# round_paws_2.net
KiCad netlist of a schematic drawn in EAGLE
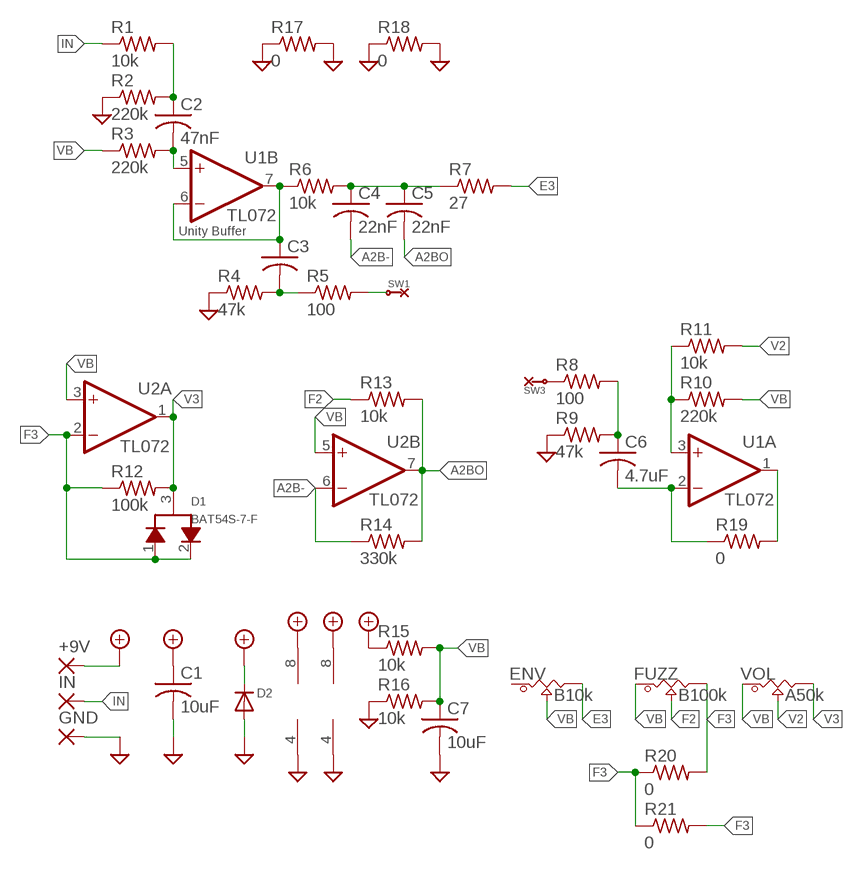
[diagram p0: schematic, sheet 1]

(export (version "E")
  (design (tool "Eeschema 10.0.6"))
  (components
    (comp (ref "+9V")
      (value "SMD2")
      (footprint "eagle-import:SMD1,27-2,54")
      (libsource (lib "eagle-import") (part "SMD2"))
    )
    (comp (ref "C1")
      (value "10uF")
      (footprint "eagle-import:C1206")
      (libsource (lib "eagle-import") (part "C-USC1206"))
    )
    (comp (ref "C2")
      (value "47nF")
      (footprint "eagle-import:C0603")
      (libsource (lib "eagle-import") (part "C-USC0603"))
    )
    (comp (ref "C3")
      (value "C-USC0603")
      (footprint "eagle-import:C0603")
      (libsource (lib "eagle-import") (part "C-USC0603"))
    )
    (comp (ref "C4")
      (value "22nF")
      (footprint "eagle-import:C0603")
      (libsource (lib "eagle-import") (part "C-USC0603"))
    )
    (comp (ref "C5")
      (value "22nF")
      (footprint "eagle-import:C0603")
      (libsource (lib "eagle-import") (part "C-USC0603"))
    )
    (comp (ref "C6")
      (value "4.7uF")
      (footprint "eagle-import:C1206")
      (libsource (lib "eagle-import") (part "C-USC1206"))
    )
    (comp (ref "C7")
      (value "10uF")
      (footprint "eagle-import:C1206")
      (libsource (lib "eagle-import") (part "C-USC1206"))
    )
    (comp (ref "D1")
      (value "BAT54S-7-F")
      (footprint "eagle-import:SOT23-3")
      (fields
        (field (name "DIGIKEY_PART_NUMBER") "BAT54S-FDITR-ND")
        (field (name "MANUFACTURER") "Diodes Incorporated")
        (field (name "CREATED_BY") "PCBLayout.com")
      )
      (libsource (lib "eagle-import") (part "BAT54S-7-F"))
    )
    (comp (ref "D2")
      (value "DIODESOD-123")
      (footprint "eagle-import:SOD-123")
      (libsource (lib "eagle-import") (part "DIODESOD-123"))
    )
    (comp (ref "ENV")
      (value "B10k")
      (footprint "eagle-import:POT_9MM_SMD")
      (libsource (lib "eagle-import") (part "POT_9MM_SMD"))
    )
    (comp (ref "FUZZ")
      (value "B100k")
      (footprint "eagle-import:POT_9MM_SMD")
      (libsource (lib "eagle-import") (part "POT_9MM_SMD"))
    )
    (comp (ref "GND")
      (value "SMD2")
      (footprint "eagle-import:SMD1,27-2,54")
      (libsource (lib "eagle-import") (part "SMD2"))
    )
    (comp (ref "IN")
      (value "SMD2")
      (footprint "eagle-import:SMD1,27-2,54")
      (libsource (lib "eagle-import") (part "SMD2"))
    )
    (comp (ref "R1")
      (value "10k")
      (footprint "eagle-import:R0603")
      (libsource (lib "eagle-import") (part "R-US_R0603"))
    )
    (comp (ref "R2")
      (value "220k")
      (footprint "eagle-import:R0603")
      (libsource (lib "eagle-import") (part "R-US_R0603"))
    )
    (comp (ref "R3")
      (value "220k")
      (footprint "eagle-import:R0603")
      (libsource (lib "eagle-import") (part "R-US_R0603"))
    )
    (comp (ref "R4")
      (value "47k")
      (footprint "eagle-import:R0603")
      (libsource (lib "eagle-import") (part "R-US_R0603"))
    )
    (comp (ref "R5")
      (value "100")
      (footprint "eagle-import:R0603")
      (libsource (lib "eagle-import") (part "R-US_R0603"))
    )
    (comp (ref "R6")
      (value "10k")
      (footprint "eagle-import:R0603")
      (libsource (lib "eagle-import") (part "R-US_R0603"))
    )
    (comp (ref "R7")
      (value "27")
      (footprint "eagle-import:R0603")
      (libsource (lib "eagle-import") (part "R-US_R0603"))
    )
    (comp (ref "R8")
      (value "100")
      (footprint "eagle-import:R0603")
      (libsource (lib "eagle-import") (part "R-US_R0603"))
    )
    (comp (ref "R9")
      (value "47k")
      (footprint "eagle-import:R0603")
      (libsource (lib "eagle-import") (part "R-US_R0603"))
    )
    (comp (ref "R10")
      (value "220k")
      (footprint "eagle-import:R0603")
      (libsource (lib "eagle-import") (part "R-US_R0603"))
    )
    (comp (ref "R11")
      (value "10k")
      (footprint "eagle-import:R0603")
      (libsource (lib "eagle-import") (part "R-US_R0603"))
    )
    (comp (ref "R12")
      (value "100k")
      (footprint "eagle-import:R0603")
      (libsource (lib "eagle-import") (part "R-US_R0603"))
    )
    (comp (ref "R13")
      (value "10k")
      (footprint "eagle-import:R0603")
      (libsource (lib "eagle-import") (part "R-US_R0603"))
    )
    (comp (ref "R14")
      (value "330k")
      (footprint "eagle-import:R0603")
      (libsource (lib "eagle-import") (part "R-US_R0603"))
    )
    (comp (ref "R15")
      (value "10k")
      (footprint "eagle-import:R0603")
      (libsource (lib "eagle-import") (part "R-US_R0603"))
    )
    (comp (ref "R16")
      (value "10k")
      (footprint "eagle-import:R0603")
      (libsource (lib "eagle-import") (part "R-US_R0603"))
    )
    (comp (ref "R17")
      (value "0")
      (footprint "eagle-import:R0402")
      (libsource (lib "eagle-import") (part "R-US_R0402"))
    )
    (comp (ref "R18")
      (value "0")
      (footprint "eagle-import:R0402")
      (libsource (lib "eagle-import") (part "R-US_R0402"))
    )
    (comp (ref "R19")
      (value "0")
      (footprint "eagle-import:R0402")
      (libsource (lib "eagle-import") (part "R-US_R0402"))
    )
    (comp (ref "R20")
      (value "0")
      (footprint "eagle-import:R0402")
      (libsource (lib "eagle-import") (part "R-US_R0402"))
    )
    (comp (ref "R21")
      (value "0")
      (footprint "eagle-import:R0402")
      (libsource (lib "eagle-import") (part "R-US_R0402"))
    )
    (comp (ref "SW1")
      (value "COM_SMD")
      (footprint "eagle-import:1PAD")
      (libsource (lib "eagle-import") (part "COM_SMD"))
    )
    (comp (ref "SW3")
      (value "COM_SMD")
      (footprint "eagle-import:1PAD")
      (libsource (lib "eagle-import") (part "COM_SMD"))
    )
    (comp (ref "U1")
      (value "TL072")
      (footprint "eagle-import:TSSOP-8")
      (libsource (lib "eagle-import") (part "TL072TSSOP"))
    )
    (comp (ref "U2")
      (value "TL072")
      (footprint "eagle-import:TSSOP-8")
      (libsource (lib "eagle-import") (part "TL072TSSOP"))
    )
    (comp (ref "VOL")
      (value "A50k")
      (footprint "eagle-import:POT_9MM_SMD")
      (libsource (lib "eagle-import") (part "POT_9MM_SMD"))
    )
  )
  (nets
    (net (code "1") (name "+9V") (class "Default")
      (node (ref "+9V") (pin "1") (pinfunction "P_1") (pintype "passive"))
      (node (ref "C1") (pin "1") (pinfunction "1_1") (pintype "passive"))
      (node (ref "D2") (pin "C") (pinfunction "C_C") (pintype "passive"))
      (node (ref "R15") (pin "1") (pinfunction "1_1") (pintype "passive"))
      (node (ref "U1") (pin "8") (pinfunction "V+_8") (pintype "power_in"))
      (node (ref "U2") (pin "8") (pinfunction "V+_8") (pintype "power_in"))
    )
    (net (code "2") (name "/A1AO") (class "Default")
      (node (ref "C6") (pin "2") (pinfunction "2_2") (pintype "passive"))
      (node (ref "R19") (pin "1") (pinfunction "1_1") (pintype "passive"))
      (node (ref "R19") (pin "2") (pinfunction "2_2") (pintype "passive"))
      (node (ref "U1") (pin "1") (pinfunction "OUT_1") (pintype "output"))
      (node (ref "U1") (pin "2") (pinfunction "-IN_2") (pintype "input"))
    )
    (net (code "3") (name "A2B-") (class "Default")
      (node (ref "C4") (pin "2") (pinfunction "2_2") (pintype "passive"))
      (node (ref "R14") (pin "1") (pinfunction "1_1") (pintype "passive"))
      (node (ref "U2") (pin "6") (pinfunction "-IN_6") (pintype "input"))
    )
    (net (code "4") (name "A2BO") (class "Default")
      (node (ref "C5") (pin "2") (pinfunction "2_2") (pintype "passive"))
      (node (ref "R13") (pin "2") (pinfunction "2_2") (pintype "passive"))
      (node (ref "R14") (pin "2") (pinfunction "2_2") (pintype "passive"))
      (node (ref "U2") (pin "7") (pinfunction "OUT_7") (pintype "output"))
    )
    (net (code "5") (name "E3") (class "Default")
      (node (ref "ENV") (pin "3") (pinfunction "3_3") (pintype "bidirectional"))
      (node (ref "R7") (pin "2") (pinfunction "2_2") (pintype "passive"))
    )
    (net (code "6") (name "F2") (class "Default")
      (node (ref "FUZZ") (pin "2") (pinfunction "2_2") (pintype "bidirectional"))
      (node (ref "R13") (pin "1") (pinfunction "1_1") (pintype "passive"))
    )
    (net (code "7") (name "F3") (class "Default")
      (node (ref "D1") (pin "1") (pinfunction "1_1") (pintype "passive"))
      (node (ref "D1") (pin "2") (pinfunction "2_2") (pintype "passive"))
      (node (ref "FUZZ") (pin "3") (pinfunction "3_3") (pintype "bidirectional"))
      (node (ref "R12") (pin "1") (pinfunction "1_1") (pintype "passive"))
      (node (ref "R20") (pin "1") (pinfunction "1_1") (pintype "passive"))
      (node (ref "R20") (pin "2") (pinfunction "2_2") (pintype "passive"))
      (node (ref "R21") (pin "1") (pinfunction "1_1") (pintype "passive"))
      (node (ref "R21") (pin "2") (pinfunction "2_2") (pintype "passive"))
      (node (ref "U2") (pin "2") (pinfunction "-IN_2") (pintype "input"))
    )
    (net (code "8") (name "GND") (class "Default")
      (node (ref "C1") (pin "2") (pinfunction "2_2") (pintype "passive"))
      (node (ref "C7") (pin "2") (pinfunction "2_2") (pintype "passive"))
      (node (ref "D2") (pin "A") (pinfunction "A_A") (pintype "passive"))
      (node (ref "GND") (pin "1") (pinfunction "P_1") (pintype "passive"))
      (node (ref "R16") (pin "1") (pinfunction "1_1") (pintype "passive"))
      (node (ref "R17") (pin "1") (pinfunction "1_1") (pintype "passive"))
      (node (ref "R17") (pin "2") (pinfunction "2_2") (pintype "passive"))
      (node (ref "R18") (pin "1") (pinfunction "1_1") (pintype "passive"))
      (node (ref "R18") (pin "2") (pinfunction "2_2") (pintype "passive"))
      (node (ref "R2") (pin "1") (pinfunction "1_1") (pintype "passive"))
      (node (ref "R4") (pin "1") (pinfunction "1_1") (pintype "passive"))
      (node (ref "R9") (pin "1") (pinfunction "1_1") (pintype "passive"))
      (node (ref "U1") (pin "4") (pinfunction "V-_4") (pintype "power_in"))
      (node (ref "U2") (pin "4") (pinfunction "V-_4") (pintype "power_in"))
    )
    (net (code "9") (name "IN") (class "Default")
      (node (ref "IN") (pin "1") (pinfunction "P_1") (pintype "passive"))
      (node (ref "R1") (pin "1") (pinfunction "1_1") (pintype "passive"))
    )
    (net (code "10") (name "Net-(C2-Pad1)") (class "Default")
      (node (ref "C2") (pin "1") (pinfunction "1_1") (pintype "passive"))
      (node (ref "R1") (pin "2") (pinfunction "2_2") (pintype "passive"))
      (node (ref "R2") (pin "2") (pinfunction "2_2") (pintype "passive"))
    )
    (net (code "11") (name "Net-(C3-Pad2)") (class "Default")
      (node (ref "C3") (pin "2") (pinfunction "2_2") (pintype "passive"))
      (node (ref "R4") (pin "2") (pinfunction "2_2") (pintype "passive"))
      (node (ref "R5") (pin "1") (pinfunction "1_1") (pintype "passive"))
    )
    (net (code "12") (name "Net-(C4-Pad1)") (class "Default")
      (node (ref "C4") (pin "1") (pinfunction "1_1") (pintype "passive"))
      (node (ref "C5") (pin "1") (pinfunction "1_1") (pintype "passive"))
      (node (ref "R6") (pin "2") (pinfunction "2_2") (pintype "passive"))
      (node (ref "R7") (pin "1") (pinfunction "1_1") (pintype "passive"))
    )
    (net (code "13") (name "Net-(C6-Pad1)") (class "Default")
      (node (ref "C6") (pin "1") (pinfunction "1_1") (pintype "passive"))
      (node (ref "R8") (pin "2") (pinfunction "2_2") (pintype "passive"))
      (node (ref "R9") (pin "2") (pinfunction "2_2") (pintype "passive"))
    )
    (net (code "14") (name "Net-(R5-Pad2)") (class "Default")
      (node (ref "R5") (pin "2") (pinfunction "2_2") (pintype "passive"))
      (node (ref "SW1") (pin "1") (pinfunction "1_1") (pintype "bidirectional"))
    )
    (net (code "15") (name "Net-(R8-Pad1)") (class "Default")
      (node (ref "R8") (pin "1") (pinfunction "1_1") (pintype "passive"))
      (node (ref "SW3") (pin "1") (pinfunction "1_1") (pintype "bidirectional"))
    )
    (net (code "16") (name "Net-(U1A-+IN)") (class "Default")
      (node (ref "R10") (pin "1") (pinfunction "1_1") (pintype "passive"))
      (node (ref "R11") (pin "1") (pinfunction "1_1") (pintype "passive"))
      (node (ref "U1") (pin "3") (pinfunction "+IN_3") (pintype "input"))
    )
    (net (code "17") (name "Net-(U1B-+IN)") (class "Default")
      (node (ref "C2") (pin "2") (pinfunction "2_2") (pintype "passive"))
      (node (ref "R3") (pin "2") (pinfunction "2_2") (pintype "passive"))
      (node (ref "U1") (pin "5") (pinfunction "+IN_5") (pintype "input"))
    )
    (net (code "18") (name "Net-(U1B--IN)") (class "Default")
      (node (ref "C3") (pin "1") (pinfunction "1_1") (pintype "passive"))
      (node (ref "R6") (pin "1") (pinfunction "1_1") (pintype "passive"))
      (node (ref "U1") (pin "6") (pinfunction "-IN_6") (pintype "input"))
      (node (ref "U1") (pin "7") (pinfunction "OUT_7") (pintype "output"))
    )
    (net (code "19") (name "V2") (class "Default")
      (node (ref "R11") (pin "2") (pinfunction "2_2") (pintype "passive"))
      (node (ref "VOL") (pin "2") (pinfunction "2_2") (pintype "bidirectional"))
    )
    (net (code "20") (name "V3") (class "Default")
      (node (ref "D1") (pin "3") (pinfunction "3_3") (pintype "passive"))
      (node (ref "R12") (pin "2") (pinfunction "2_2") (pintype "passive"))
      (node (ref "U2") (pin "1") (pinfunction "OUT_1") (pintype "output"))
      (node (ref "VOL") (pin "3") (pinfunction "3_3") (pintype "bidirectional"))
    )
    (net (code "21") (name "VB") (class "Default")
      (node (ref "C7") (pin "1") (pinfunction "1_1") (pintype "passive"))
      (node (ref "ENV") (pin "2") (pinfunction "2_2") (pintype "bidirectional"))
      (node (ref "FUZZ") (pin "1") (pinfunction "1_1") (pintype "bidirectional"))
      (node (ref "R10") (pin "2") (pinfunction "2_2") (pintype "passive"))
      (node (ref "R15") (pin "2") (pinfunction "2_2") (pintype "passive"))
      (node (ref "R16") (pin "2") (pinfunction "2_2") (pintype "passive"))
      (node (ref "R3") (pin "1") (pinfunction "1_1") (pintype "passive"))
      (node (ref "U2") (pin "3") (pinfunction "+IN_3") (pintype "input"))
      (node (ref "U2") (pin "5") (pinfunction "+IN_5") (pintype "input"))
      (node (ref "VOL") (pin "1") (pinfunction "1_1") (pintype "bidirectional"))
    )
    (net (code "22") (name "unconnected-(ENV-Pad1)") (class "Default")
      (node (ref "ENV") (pin "1") (pinfunction "1_1") (pintype "bidirectional"))
    )
  )
)
